# fastedge-ADCMP572.net
KiCad netlist of a schematic drawn in Altium Designer
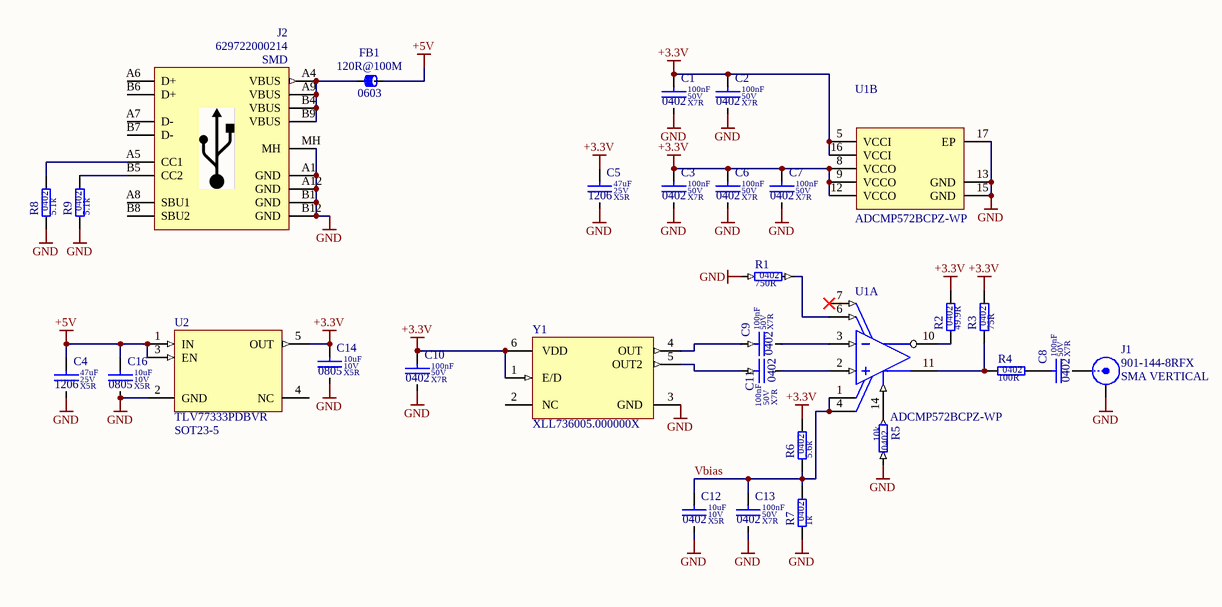
[diagram p0: fastedge-ADCMP572.SchDoc]

(export (version "E")
  (design (tool "Eeschema 10.0.6"))
  (components
    (comp (ref "C1")
      (value "100nF")
      (footprint "C_0402_1005")
      (description "Capacitor")
      (fields
        (field (name "DIELECTRIC") "X7R")
        (field (name "VOLTAGE") "50V")
        (field (name "SCH_FOOTPRINT") "0402")
        (field (name "PART NUMBER") "C_100nF_50V_X7R_0402_10")
        (field (name "MANUFACTURER") "Murata")
      )
      (libsource (lib "Library") (part "C"))
    )
    (comp (ref "C2")
      (value "100nF")
      (footprint "C_0402_1005")
      (description "Capacitor")
      (fields
        (field (name "DIELECTRIC") "X7R")
        (field (name "VOLTAGE") "50V")
        (field (name "SCH_FOOTPRINT") "0402")
        (field (name "PART NUMBER") "C_100nF_50V_X7R_0402_10")
        (field (name "MANUFACTURER") "Murata")
      )
      (libsource (lib "Library") (part "C"))
    )
    (comp (ref "C3")
      (value "100nF")
      (footprint "C_0402_1005")
      (description "Capacitor")
      (fields
        (field (name "DIELECTRIC") "X7R")
        (field (name "VOLTAGE") "50V")
        (field (name "SCH_FOOTPRINT") "0402")
        (field (name "PART NUMBER") "C_100nF_50V_X7R_0402_10")
        (field (name "MANUFACTURER") "Murata")
      )
      (libsource (lib "Library") (part "C"))
    )
    (comp (ref "C4")
      (value "47uF")
      (footprint "C_1206_3216")
      (description "Capacitor")
      (fields
        (field (name "DIELECTRIC") "X5R")
        (field (name "VOLTAGE") "25V")
        (field (name "SCH_FOOTPRINT") "1206")
        (field (name "PART NUMBER") "C_47uF_25V_X5R_1206_20")
        (field (name "MANUFACTURER") "TDK")
      )
      (libsource (lib "Library") (part "C"))
    )
    (comp (ref "C5")
      (value "47uF")
      (footprint "C_1206_3216")
      (description "Capacitor")
      (fields
        (field (name "DIELECTRIC") "X5R")
        (field (name "VOLTAGE") "25V")
        (field (name "SCH_FOOTPRINT") "1206")
        (field (name "PART NUMBER") "C_47uF_25V_X5R_1206_20")
        (field (name "MANUFACTURER") "TDK")
      )
      (libsource (lib "Library") (part "C"))
    )
    (comp (ref "C6")
      (value "100nF")
      (footprint "C_0402_1005")
      (description "Capacitor")
      (fields
        (field (name "DIELECTRIC") "X7R")
        (field (name "VOLTAGE") "50V")
        (field (name "SCH_FOOTPRINT") "0402")
        (field (name "PART NUMBER") "C_100nF_50V_X7R_0402_10")
        (field (name "MANUFACTURER") "Murata")
      )
      (libsource (lib "Library") (part "C"))
    )
    (comp (ref "C7")
      (value "100nF")
      (footprint "C_0402_1005")
      (description "Capacitor")
      (fields
        (field (name "DIELECTRIC") "X7R")
        (field (name "VOLTAGE") "50V")
        (field (name "SCH_FOOTPRINT") "0402")
        (field (name "PART NUMBER") "C_100nF_50V_X7R_0402_10")
        (field (name "MANUFACTURER") "Murata")
      )
      (libsource (lib "Library") (part "C"))
    )
    (comp (ref "C8")
      (value "100nF")
      (footprint "C_0402_1005")
      (description "Capacitor")
      (fields
        (field (name "DIELECTRIC") "X7R")
        (field (name "VOLTAGE") "50V")
        (field (name "SCH_FOOTPRINT") "0402")
        (field (name "PART NUMBER") "C_100nF_50V_X7R_0402_10")
        (field (name "MANUFACTURER") "Murata")
      )
      (libsource (lib "Library") (part "C"))
    )
    (comp (ref "C9")
      (value "100nF")
      (footprint "C_0402_1005")
      (description "Capacitor")
      (fields
        (field (name "DIELECTRIC") "X7R")
        (field (name "VOLTAGE") "50V")
        (field (name "SCH_FOOTPRINT") "0402")
        (field (name "PART NUMBER") "C_100nF_50V_X7R_0402_10")
        (field (name "MANUFACTURER") "Murata")
      )
      (libsource (lib "") (part "C_1"))
    )
    (comp (ref "C10")
      (value "100nF")
      (footprint "C_0402_1005")
      (description "Capacitor")
      (fields
        (field (name "DIELECTRIC") "X7R")
        (field (name "VOLTAGE") "50V")
        (field (name "SCH_FOOTPRINT") "0402")
        (field (name "PART NUMBER") "C_100nF_50V_X7R_0402_10")
        (field (name "MANUFACTURER") "Murata")
      )
      (libsource (lib "Library") (part "C"))
    )
    (comp (ref "C11")
      (value "100nF")
      (footprint "C_0402_1005")
      (description "Capacitor")
      (fields
        (field (name "DIELECTRIC") "X7R")
        (field (name "VOLTAGE") "50V")
        (field (name "SCH_FOOTPRINT") "0402")
        (field (name "PART NUMBER") "C_100nF_50V_X7R_0402_10")
        (field (name "MANUFACTURER") "Murata")
      )
      (libsource (lib "") (part "C_1"))
    )
    (comp (ref "C12")
      (value "10uF")
      (footprint "C_0402_1005")
      (description "Capacitor")
      (fields
        (field (name "DIELECTRIC") "X5R")
        (field (name "VOLTAGE") "10V")
        (field (name "SCH_FOOTPRINT") "0402")
        (field (name "PART NUMBER") "C_10uF_10V_X5R_0402_20")
        (field (name "MANUFACTURER") "Murata")
      )
      (libsource (lib "Library") (part "C"))
    )
    (comp (ref "C13")
      (value "100nF")
      (footprint "C_0402_1005")
      (description "Capacitor")
      (fields
        (field (name "DIELECTRIC") "X7R")
        (field (name "VOLTAGE") "50V")
        (field (name "SCH_FOOTPRINT") "0402")
        (field (name "PART NUMBER") "C_100nF_50V_X7R_0402_10")
        (field (name "MANUFACTURER") "Murata")
      )
      (libsource (lib "Library") (part "C"))
    )
    (comp (ref "C14")
      (value "10uF")
      (footprint "C_0805_2012")
      (description "Capacitor")
      (fields
        (field (name "DIELECTRIC") "X5R")
        (field (name "VOLTAGE") "10V")
        (field (name "SCH_FOOTPRINT") "0805")
        (field (name "PART NUMBER") "C_10uF_10V_X5R_0805_10")
        (field (name "MANUFACTURER") "Kemet")
      )
      (libsource (lib "Library") (part "C"))
    )
    (comp (ref "C16")
      (value "10uF")
      (footprint "C_0805_2012")
      (description "Capacitor")
      (fields
        (field (name "DIELECTRIC") "X5R")
        (field (name "VOLTAGE") "10V")
        (field (name "SCH_FOOTPRINT") "0805")
        (field (name "PART NUMBER") "C_10uF_10V_X5R_0805_10")
        (field (name "MANUFACTURER") "Kemet")
      )
      (libsource (lib "Library") (part "C"))
    )
    (comp (ref "FB1")
      (value "120R@100M")
      (footprint "FB_0603_1608")
      (description "Ferrite Bead")
      (fields
        (field (name "SCH_FOOTPRINT") "0603")
        (field (name "PART NUMBER") "FB_BLM18AG121SH1D")
        (field (name "MANUFACTURER") "Murata")
      )
      (libsource (lib "Library") (part "FB"))
    )
    (comp (ref "J1")
      (value "901-144-8RFX")
      (footprint "J_SMA_VERTICAL")
      (description "SMA connector")
      (fields
        (field (name "SCH_FOOTPRINT") "SMA VERTICAL")
        (field (name "PART NUMBER") "J_SMA_VERTICAL")
        (field (name "MANUFACTURER") "Amphenol")
      )
      (libsource (lib "Library") (part "J_SMA"))
    )
    (comp (ref "J2")
      (value "629722000214")
      (footprint "J_USB_C_629722000214")
      (fields
        (field (name "SCH_FOOTPRINT") "SMD")
        (field (name "PART NUMBER") "J_USB_C_629722000214")
        (field (name "MANUFACTURER") "Wurth")
        (field (name "Comment") "USB 2.0 Type C")
      )
      (libsource (lib "Library") (part "J_USB_C_16pin"))
    )
    (comp (ref "R1")
      (value "750R")
      (footprint "R_0402_1005")
      (fields
        (field (name "SCH_FOOTPRINT") "0402")
        (field (name "PART NUMBER") "R_750R_0402_1")
        (field (name "VOLTAGE") "50V")
        (field (name "POWER") "100mW")
      )
      (libsource (lib "") (part "R_1"))
    )
    (comp (ref "R2")
      (value "49.9R")
      (footprint "R_0402_1005")
      (fields
        (field (name "SCH_FOOTPRINT") "0402")
        (field (name "PART NUMBER") "R_49.9R_0402_1_AECQ0")
        (field (name "VOLTAGE") "50V")
        (field (name "POWER") "100mW")
      )
      (libsource (lib "Library") (part "R"))
    )
    (comp (ref "R3")
      (value "75R")
      (footprint "R_0402_1005")
      (fields
        (field (name "SCH_FOOTPRINT") "0402")
        (field (name "PART NUMBER") "R_75R_0402_1_AECQ0")
        (field (name "VOLTAGE") "50V")
        (field (name "POWER") "100mW")
      )
      (libsource (lib "Library") (part "R"))
    )
    (comp (ref "R4")
      (value "100R")
      (footprint "R_0402_1005")
      (fields
        (field (name "SCH_FOOTPRINT") "0402")
        (field (name "PART NUMBER") "R_100R_0402_1_AECQ0")
        (field (name "VOLTAGE") "50V")
        (field (name "POWER") "100mW")
      )
      (libsource (lib "Library") (part "R"))
    )
    (comp (ref "R5")
      (value "10k")
      (footprint "R_0402_1005")
      (fields
        (field (name "SCH_FOOTPRINT") "0402")
        (field (name "PART NUMBER") "R_10k_0402_1")
        (field (name "VOLTAGE") "50V")
        (field (name "POWER") "63mW")
      )
      (libsource (lib "") (part "R_2"))
    )
    (comp (ref "R6")
      (value "5.6k")
      (footprint "R_0402_1005")
      (fields
        (field (name "SCH_FOOTPRINT") "0402")
        (field (name "PART NUMBER") "R_5.6k_0402_1")
        (field (name "VOLTAGE") "50V")
        (field (name "POWER") "63mW")
      )
      (libsource (lib "Library") (part "R"))
    )
    (comp (ref "R7")
      (value "1k")
      (footprint "R_0402_1005")
      (fields
        (field (name "SCH_FOOTPRINT") "0402")
        (field (name "PART NUMBER") "R_1k_0402_1")
        (field (name "VOLTAGE") "50V")
        (field (name "POWER") "63mW")
      )
      (libsource (lib "Library") (part "R"))
    )
    (comp (ref "R8")
      (value "5.1k")
      (footprint "R_0402_1005")
      (fields
        (field (name "SCH_FOOTPRINT") "0402")
        (field (name "PART NUMBER") "R_5.1k_0402_1")
        (field (name "VOLTAGE") "50V")
        (field (name "POWER") "63mW")
      )
      (libsource (lib "Library") (part "R"))
    )
    (comp (ref "R9")
      (value "5.1k")
      (footprint "R_0402_1005")
      (fields
        (field (name "SCH_FOOTPRINT") "0402")
        (field (name "PART NUMBER") "R_5.1k_0402_1")
        (field (name "VOLTAGE") "50V")
        (field (name "POWER") "63mW")
      )
      (libsource (lib "Library") (part "R"))
    )
    (comp (ref "U1")
      (value "ADCMP572BCPZ-WP")
      (footprint "ADI-CP-16-3_L")
      (fields (field (name "MANUFACTURER") "Analog Devices"))
      (libsource (lib "Altium Content Vault") (part "ADI-ADCMP572-CP-16-3"))
    )
    (comp (ref "U2")
      (value "TLV77333PDBVR")
      (footprint "SOT23-5_SC74A_SOT753_M")
      (description "TPS7A25")
      (fields
        (field (name "SCH_FOOTPRINT") "SOT23-5")
        (field (name "PART NUMBER") "VL_TLV77333PDBVR")
        (field (name "VOLTAGE") "3.3V")
      )
      (libsource (lib "Library") (part "VL_TLV773xxPDBVR"))
    )
    (comp (ref "Y1")
      (value "XLL736005.000000X")
      (footprint "JU6_MFG")
      (description "Renesas XL Family of Low Phase Noise Quartz-based PLL Oscillators")
      (libsource (lib "Altium Content Vault") (part "57af4c0192cbe41ed51f7d5823f7c83"))
    )
  )
  (nets
    (net (code "1") (name "+3.3V") (class "Default")
      (node (ref "C1") (pin "1") (pinfunction "1_1") (pintype "passive"))
      (node (ref "C10") (pin "1") (pinfunction "1_1") (pintype "passive"))
      (node (ref "C14") (pin "1") (pinfunction "1_1") (pintype "passive"))
      (node (ref "C2") (pin "1") (pinfunction "1_1") (pintype "passive"))
      (node (ref "C3") (pin "1") (pinfunction "1_1") (pintype "passive"))
      (node (ref "C5") (pin "1") (pinfunction "1_1") (pintype "passive"))
      (node (ref "C6") (pin "1") (pinfunction "1_1") (pintype "passive"))
      (node (ref "C7") (pin "1") (pinfunction "1_1") (pintype "passive"))
      (node (ref "R2") (pin "2") (pinfunction "2_2") (pintype "passive"))
      (node (ref "R3") (pin "2") (pinfunction "2_2") (pintype "passive"))
      (node (ref "R6") (pin "2") (pinfunction "2_2") (pintype "passive"))
      (node (ref "U1") (pin "12") (pinfunction "VCCO_12") (pintype "power_in"))
      (node (ref "U1") (pin "16") (pinfunction "VCCI_16") (pintype "power_in"))
      (node (ref "U1") (pin "5") (pinfunction "VCCI_5") (pintype "power_in"))
      (node (ref "U1") (pin "8") (pinfunction "VCCO_8") (pintype "power_in"))
      (node (ref "U1") (pin "9") (pinfunction "VCCO_9") (pintype "power_in"))
      (node (ref "U2") (pin "5") (pinfunction "OUT_5") (pintype "output"))
      (node (ref "Y1") (pin "1") (pinfunction "E/D_1") (pintype "input"))
      (node (ref "Y1") (pin "6") (pinfunction "VDD_6") (pintype "power_in"))
    )
    (net (code "2") (name "+5V") (class "Default")
      (node (ref "C16") (pin "1") (pinfunction "1_1") (pintype "passive"))
      (node (ref "C4") (pin "1") (pinfunction "1_1") (pintype "passive"))
      (node (ref "FB1") (pin "2") (pintype "passive"))
      (node (ref "U2") (pin "1") (pinfunction "IN_1") (pintype "input"))
      (node (ref "U2") (pin "3") (pinfunction "EN_3") (pintype "input"))
    )
    (net (code "3") (name "/Vbias") (class "Default")
      (node (ref "C12") (pin "1") (pinfunction "1_1") (pintype "passive"))
      (node (ref "C13") (pin "1") (pinfunction "1_1") (pintype "passive"))
      (node (ref "R6") (pin "1") (pinfunction "1_1") (pintype "passive"))
      (node (ref "R7") (pin "2") (pinfunction "2_2") (pintype "passive"))
      (node (ref "U1") (pin "1") (pinfunction "VTP_1") (pintype "passive"))
      (node (ref "U1") (pin "4") (pinfunction "VTN_4") (pintype "passive"))
    )
    (net (code "4") (name "GND") (class "Default")
      (node (ref "C1") (pin "2") (pinfunction "2_2") (pintype "passive"))
      (node (ref "C10") (pin "2") (pinfunction "2_2") (pintype "passive"))
      (node (ref "C12") (pin "2") (pinfunction "2_2") (pintype "passive"))
      (node (ref "C13") (pin "2") (pinfunction "2_2") (pintype "passive"))
      (node (ref "C14") (pin "2") (pinfunction "2_2") (pintype "passive"))
      (node (ref "C16") (pin "2") (pinfunction "2_2") (pintype "passive"))
      (node (ref "C2") (pin "2") (pinfunction "2_2") (pintype "passive"))
      (node (ref "C3") (pin "2") (pinfunction "2_2") (pintype "passive"))
      (node (ref "C4") (pin "2") (pinfunction "2_2") (pintype "passive"))
      (node (ref "C5") (pin "2") (pinfunction "2_2") (pintype "passive"))
      (node (ref "C6") (pin "2") (pinfunction "2_2") (pintype "passive"))
      (node (ref "C7") (pin "2") (pinfunction "2_2") (pintype "passive"))
      (node (ref "J1") (pin "GND") (pinfunction "GND_GND") (pintype "power_in"))
      (node (ref "J2") (pin "A1") (pinfunction "GND_A1") (pintype "power_in"))
      (node (ref "J2") (pin "A12") (pinfunction "GND_A12") (pintype "power_in"))
      (node (ref "J2") (pin "B1") (pinfunction "GND_B1") (pintype "power_in"))
      (node (ref "J2") (pin "B12") (pinfunction "GND_B12") (pintype "power_in"))
      (node (ref "J2") (pin "MH") (pinfunction "MH_MH") (pintype "passive"))
      (node (ref "R1") (pin "1") (pinfunction "1_1") (pintype "input"))
      (node (ref "R5") (pin "2") (pinfunction "2_2") (pintype "input"))
      (node (ref "R7") (pin "1") (pinfunction "1_1") (pintype "passive"))
      (node (ref "R8") (pin "1") (pinfunction "1_1") (pintype "passive"))
      (node (ref "R9") (pin "1") (pinfunction "1_1") (pintype "passive"))
      (node (ref "U1") (pin "13") (pinfunction "GND_13") (pintype "power_in"))
      (node (ref "U1") (pin "15") (pinfunction "GND_15") (pintype "power_in"))
      (node (ref "U1") (pin "17") (pinfunction "EP_17") (pintype "passive"))
      (node (ref "U2") (pin "2") (pinfunction "GND_2") (pintype "power_in"))
      (node (ref "Y1") (pin "3") (pinfunction "GND_3") (pintype "power_in"))
    )
    (net (code "5") (name "Net-(C8-Pad1)") (class "Default")
      (node (ref "C8") (pin "1") (pinfunction "1_1") (pintype "passive"))
      (node (ref "R4") (pin "2") (pinfunction "2_2") (pintype "passive"))
    )
    (net (code "6") (name "Net-(FB1-Pad1)") (class "Default")
      (node (ref "FB1") (pin "1") (pintype "passive"))
      (node (ref "J2") (pin "A4") (pinfunction "VBUS_A4") (pintype "output"))
      (node (ref "J2") (pin "A9") (pinfunction "VBUS_A9") (pintype "passive"))
      (node (ref "J2") (pin "B4") (pinfunction "VBUS_B4") (pintype "passive"))
      (node (ref "J2") (pin "B9") (pinfunction "VBUS_B9") (pintype "passive"))
    )
    (net (code "7") (name "Net-(J1-X)") (class "Default")
      (node (ref "C8") (pin "2") (pinfunction "2_2") (pintype "passive"))
      (node (ref "J1") (pin "1") (pinfunction "X_1") (pintype "passive"))
    )
    (net (code "8") (name "Net-(J2-CC1)") (class "Default")
      (node (ref "J2") (pin "A5") (pinfunction "CC1_A5") (pintype "passive"))
      (node (ref "R8") (pin "2") (pinfunction "2_2") (pintype "passive"))
    )
    (net (code "9") (name "Net-(J2-CC2)") (class "Default")
      (node (ref "J2") (pin "B5") (pinfunction "CC2_B5") (pintype "passive"))
      (node (ref "R9") (pin "2") (pinfunction "2_2") (pintype "passive"))
    )
    (net (code "10") (name "Net-(U1A-HYS)") (class "Default")
      (node (ref "R5") (pin "1") (pinfunction "1_1") (pintype "output"))
      (node (ref "U1") (pin "14") (pinfunction "HYS_14") (pintype "input"))
    )
    (net (code "11") (name "Net-(U1A-Q)") (class "Default")
      (node (ref "R3") (pin "1") (pinfunction "1_1") (pintype "passive"))
      (node (ref "R4") (pin "1") (pinfunction "1_1") (pintype "passive"))
      (node (ref "U1") (pin "11") (pinfunction "Q_11") (pintype "open_emitter"))
    )
    (net (code "12") (name "Net-(U1A-VN)") (class "Default")
      (node (ref "C9") (pin "2") (pinfunction "2_2") (pintype "output"))
      (node (ref "U1") (pin "3") (pinfunction "VN_3") (pintype "input"))
    )
    (net (code "13") (name "Net-(U1A-VP)") (class "Default")
      (node (ref "C11") (pin "2") (pinfunction "2_2") (pintype "output"))
      (node (ref "U1") (pin "2") (pinfunction "VP_2") (pintype "input"))
    )
    (net (code "14") (name "Net-(U1A-~{LE})") (class "Default")
      (node (ref "R1") (pin "2") (pinfunction "2_2") (pintype "output"))
      (node (ref "U1") (pin "6") (pinfunction "~{LE}_6") (pintype "input"))
    )
    (net (code "15") (name "Net-(U1A-~{Q})") (class "Default")
      (node (ref "R2") (pin "1") (pinfunction "1_1") (pintype "passive"))
      (node (ref "U1") (pin "10") (pinfunction "~{Q}_10") (pintype "open_emitter"))
    )
    (net (code "16") (name "Net-(Y1-OUT)") (class "Default")
      (node (ref "C9") (pin "1") (pinfunction "1_1") (pintype "input"))
      (node (ref "Y1") (pin "4") (pinfunction "OUT_4") (pintype "output"))
    )
    (net (code "17") (name "Net-(Y1-OUT2)") (class "Default")
      (node (ref "C11") (pin "1") (pinfunction "1_1") (pintype "input"))
      (node (ref "Y1") (pin "5") (pinfunction "OUT2_5") (pintype "output"))
    )
    (net (code "18") (name "unconnected-(J2-D+-PadA6)") (class "Default")
      (node (ref "J2") (pin "A6") (pinfunction "D+_A6") (pintype "passive"))
    )
    (net (code "19") (name "unconnected-(J2-D+-PadB6)") (class "Default")
      (node (ref "J2") (pin "B6") (pinfunction "D+_B6") (pintype "passive"))
    )
    (net (code "20") (name "unconnected-(J2-D--PadA7)") (class "Default")
      (node (ref "J2") (pin "A7") (pinfunction "D-_A7") (pintype "passive"))
    )
    (net (code "21") (name "unconnected-(J2-D--PadB7)") (class "Default")
      (node (ref "J2") (pin "B7") (pinfunction "D-_B7") (pintype "passive"))
    )
    (net (code "22") (name "unconnected-(J2-SBU1-PadA8)") (class "Default")
      (node (ref "J2") (pin "A8") (pinfunction "SBU1_A8") (pintype "passive"))
    )
    (net (code "23") (name "unconnected-(J2-SBU2-PadB8)") (class "Default")
      (node (ref "J2") (pin "B8") (pinfunction "SBU2_B8") (pintype "passive"))
    )
    (net (code "24") (name "unconnected-(U1A-LE-Pad7)") (class "Default")
      (node (ref "U1") (pin "7") (pinfunction "LE_7") (pintype "input+no_connect"))
    )
    (net (code "25") (name "unconnected-(U2-NC-Pad4)") (class "Default")
      (node (ref "U2") (pin "4") (pinfunction "NC_4") (pintype "passive"))
    )
    (net (code "26") (name "unconnected-(Y1-NC-Pad2)") (class "Default")
      (node (ref "Y1") (pin "2") (pinfunction "NC_2") (pintype "passive"))
    )
  )
)
